# Clock.net
KiCad netlist of a schematic drawn in Altium Designer
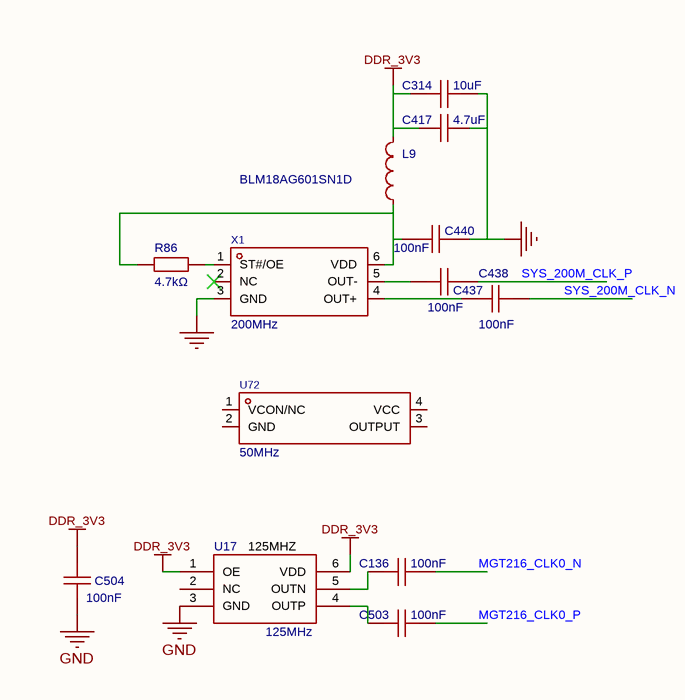
[diagram p0: Clock.schdoc]

(export (version "E")
  (design (tool "Eeschema 10.0.6"))
  (components
    (comp (ref "C136")
      (value "100nF")
      (footprint "C0402")
      (description "容值:100nF;精度:±10%;额定电压:50V;材质(温度系数):X7R;")
      (fields (field (name "MANUFACTURER") "FH(风华)") (field (name "MANUFACTURERPART") "0402B104K500NT"))
      (libsource (lib "altium-import") (part "root_2_0402B104K500NT_"))
    )
    (comp (ref "C314")
      (value "10uF")
      (footprint "C0603")
      (description "容值:10uF;精度:±10%;额定电压:10V;材质(温度系数):X5R;")
      (fields
        (field (name "MANUFACTURER") "SAMSUNG(三星)")
        (field (name "MANUFACTURER PART") "CL10A106KP8NNNC")
      )
      (libsource (lib "altium-import") (part "root_2_CL10A106KP8NNNC_"))
    )
    (comp (ref "C417")
      (value "4.7uF")
      (footprint "C0603")
      (description "容值:4.7uF;精度:±10%;额定电压:16V;材质(温度系数):X5R;")
      (fields
        (field (name "MANUFACTURER PART") "CL10A475KO8NNNC")
        (field (name "MANUFACTURER") "SAMSUNG(三星)")
      )
      (libsource (lib "altium-import") (part "root_0_CL10A475KO8NNNC_"))
    )
    (comp (ref "C437")
      (value "100nF")
      (footprint "C0402")
      (description "容值:100nF;精度:±10%;额定电压:50V;材质(温度系数):X7R;")
      (fields
        (field (name "MANUFACTURER") "muRata(村田)")
        (field (name "MANUFACTURER PART") "GRM155R71H104KE14D")
      )
      (libsource (lib "altium-import") (part "root_0_GRM155R71H104KE14D_"))
    )
    (comp (ref "C438")
      (value "100nF")
      (footprint "C0402")
      (description "容值:100nF;精度:±10%;额定电压:50V;材质(温度系数):X7R;")
      (fields
        (field (name "MANUFACTURER") "muRata(村田)")
        (field (name "MANUFACTURER PART") "GRM155R71H104KE14D")
      )
      (libsource (lib "altium-import") (part "root_0_GRM155R71H104KE14D_"))
    )
    (comp (ref "C440")
      (value "100nF")
      (footprint "C0402")
      (description "容值:100nF;精度:±10%;额定电压:50V;材质(温度系数):X7R;")
      (fields
        (field (name "MANUFACTURER") "muRata(村田)")
        (field (name "MANUFACTURER PART") "GRM155R71H104KE14D")
      )
      (libsource (lib "altium-import") (part "root_0_GRM155R71H104KE14D_"))
    )
    (comp (ref "C503")
      (value "100nF")
      (footprint "C0402")
      (description "容值:100nF;精度:±10%;额定电压:50V;材质(温度系数):X7R;")
      (fields (field (name "MANUFACTURER") "FH(风华)") (field (name "MANUFACTURERPART") "0402B104K500NT"))
      (libsource (lib "altium-import") (part "root_2_0402B104K500NT_"))
    )
    (comp (ref "C504")
      (value "100nF")
      (footprint "C0402")
      (description "容值:100nF;精度:±10%;额定电压:50V;材质(温度系数):X7R;")
      (fields (field (name "MANUFACTURER") "FH(风华)") (field (name "MANUFACTURERPART") "0402B104K500NT"))
      (libsource (lib "altium-import") (part "root_3_0402B104K500NT_"))
    )
    (comp (ref "L9")
      (value "BLM18AG601SN1D")
      (footprint "L0603")
      (description "标称阻抗@测试频率:600Ω@100MHz;误差:±25%;直流电阻(RDC):380mΩ;")
      (fields (field (name "MANUFACTURER") "muRata(村田)") (field (name "TOLERANCE") "±25%"))
      (libsource (lib "altium-import") (part "root_1_BLM18AG601SN1D_"))
    )
    (comp (ref "R86")
      (value "4.7kΩ")
      (footprint "R0603")
      (description "电阻类型:厚膜电阻;阻值:4.7kΩ;精度:±1%;功率:100mW;最大工作电压:75V;温度系数:±100ppm/℃;")
      (fields
        (field (name "MANUFACTURER") "UNI-ROYAL(厚声)")
        (field (name "MANUFACTURER PART") "0603WAF4701T5E")
      )
      (libsource (lib "altium-import") (part "root_2_0603WAF4701T5E_"))
    )
    (comp (ref "U17")
      (value "125MHz")
      (footprint "OSC-SMD_6P-L5.0-W3.2-P1.27-BL")
      (description "频率:125MHz;频率稳定度(全温):±20ppm;输出模式:LVDS;供电电压:3.3V;")
      (fields
        (field (name "MANUFACTURER") "SITIME")
        (field (name "MANUFACTURERPART") "SiT9120AI-2C1-33E125.000000")
      )
      (libsource (lib "altium-import") (part "root_0_SiT9120AI-2C1-33E125.000000_"))
    )
    (comp (ref "U72")
      (value "50MHz")
      (footprint "OSC-SMD_4P-L7.0-W5.0-BL")
      (description "频率:50MHz;频率稳定度(全温):±1ppm;输出模式:方波;工作电压:3.3V;")
      (fields
        (field (name "MANUFACTURER") "XTALTQ(恒晶科技)")
        (field (name "MANUFACTURER PART") "NT0507BH3I106BA50")
      )
      (libsource (lib "altium-import") (part "root_0_NT0507BH3I106BA50_"))
    )
    (comp (ref "X1")
      (value "200MHz")
      (footprint "OSC-SMD_6P-L7.0-W5.0-BL")
      (description "频率:200MHz;频率稳定度(全温):±25ppm;输出模式:LVDS;供电电压:3.3V;")
      (fields
        (field (name "MANUFACTURER") "SITIME")
        (field (name "MANUFACTURER PART") "SiT9102AI-282N33E200")
      )
      (libsource (lib "altium-import") (part "root_0_SiT9102AI-282N33E200_"))
    )
  )
  (nets
    (net (code "1") (name "/MGT216_CLK0_N") (class "Default")
      (node (ref "C136") (pin "1") (pinfunction "1_1") (pintype "passive"))
    )
    (net (code "2") (name "/MGT216_CLK0_P") (class "Default")
      (node (ref "C503") (pin "1") (pinfunction "1_1") (pintype "passive"))
    )
    (net (code "3") (name "/SYS_200M_CLK_N") (class "Default")
      (node (ref "C438") (pin "2") (pinfunction "2_2") (pintype "passive"))
    )
    (net (code "4") (name "/SYS_200M_CLK_P") (class "Default")
      (node (ref "C437") (pin "2") (pinfunction "2_2") (pintype "passive"))
    )
    (net (code "5") (name "DDR_3V3") (class "Default")
      (node (ref "C314") (pin "2") (pinfunction "2_2") (pintype "passive"))
      (node (ref "C417") (pin "1") (pinfunction "1_1") (pintype "passive"))
      (node (ref "C504") (pin "1") (pinfunction "1_1") (pintype "passive"))
      (node (ref "L9") (pin "2") (pinfunction "2_2") (pintype "passive"))
      (node (ref "U17") (pin "1") (pinfunction "OE_1") (pintype "passive"))
      (node (ref "U17") (pin "6") (pinfunction "VDD_6") (pintype "passive"))
    )
    (net (code "6") (name "GND") (class "Default")
      (node (ref "C314") (pin "1") (pinfunction "1_1") (pintype "passive"))
      (node (ref "C417") (pin "2") (pinfunction "2_2") (pintype "passive"))
      (node (ref "C440") (pin "2") (pinfunction "2_2") (pintype "passive"))
      (node (ref "C504") (pin "2") (pinfunction "2_2") (pintype "passive"))
      (node (ref "U17") (pin "3") (pinfunction "GND_3") (pintype "passive"))
      (node (ref "X1") (pin "3") (pinfunction "GND_3") (pintype "passive"))
    )
    (net (code "7") (name "Net-(U17-OUTN)") (class "Default")
      (node (ref "C136") (pin "2") (pinfunction "2_2") (pintype "passive"))
      (node (ref "U17") (pin "5") (pinfunction "OUTN_5") (pintype "passive"))
    )
    (net (code "8") (name "Net-(U17-OUTP)") (class "Default")
      (node (ref "C503") (pin "2") (pinfunction "2_2") (pintype "passive"))
      (node (ref "U17") (pin "4") (pinfunction "OUTP_4") (pintype "passive"))
    )
    (net (code "9") (name "Net-(X1-OUT+)") (class "Default")
      (node (ref "C438") (pin "1") (pinfunction "1_1") (pintype "passive"))
      (node (ref "X1") (pin "4") (pinfunction "OUT+_4") (pintype "passive"))
    )
    (net (code "10") (name "Net-(X1-OUT-)") (class "Default")
      (node (ref "C437") (pin "1") (pinfunction "1_1") (pintype "passive"))
      (node (ref "X1") (pin "5") (pinfunction "OUT-_5") (pintype "passive"))
    )
    (net (code "11") (name "Net-(X1-ST#{slash}OE)") (class "Default")
      (node (ref "R86") (pin "1") (pinfunction "1_1") (pintype "passive"))
      (node (ref "X1") (pin "1") (pinfunction "ST#/OE_1") (pintype "passive"))
    )
    (net (code "12") (name "Net-(X1-VDD)") (class "Default")
      (node (ref "C440") (pin "1") (pinfunction "1_1") (pintype "passive"))
      (node (ref "L9") (pin "1") (pinfunction "1_1") (pintype "passive"))
      (node (ref "R86") (pin "2") (pinfunction "2_2") (pintype "passive"))
      (node (ref "X1") (pin "6") (pinfunction "VDD_6") (pintype "passive"))
    )
    (net (code "13") (name "unconnected-(U17-NC-Pad2)") (class "Default")
      (node (ref "U17") (pin "2") (pinfunction "NC_2") (pintype "passive"))
    )
    (net (code "14") (name "unconnected-(U72-GND-Pad2)") (class "Default")
      (node (ref "U72") (pin "2") (pinfunction "GND_2") (pintype "passive"))
    )
    (net (code "15") (name "unconnected-(U72-OUTPUT-Pad3)") (class "Default")
      (node (ref "U72") (pin "3") (pinfunction "OUTPUT_3") (pintype "passive"))
    )
    (net (code "16") (name "unconnected-(U72-VCC-Pad4)") (class "Default")
      (node (ref "U72") (pin "4") (pinfunction "VCC_4") (pintype "passive"))
    )
    (net (code "17") (name "unconnected-(U72-VCON{slash}NC-Pad1)") (class "Default")
      (node (ref "U72") (pin "1") (pinfunction "VCON/NC_1") (pintype "passive"))
    )
    (net (code "18") (name "unconnected-(X1-NC-Pad2)") (class "Default")
      (node (ref "X1") (pin "2") (pinfunction "NC_2") (pintype "passive+no_connect"))
    )
  )
)
